# PCM2706_Bus_Powered_USB_DAC_3.net
KiCad netlist of a schematic drawn in Altium Designer
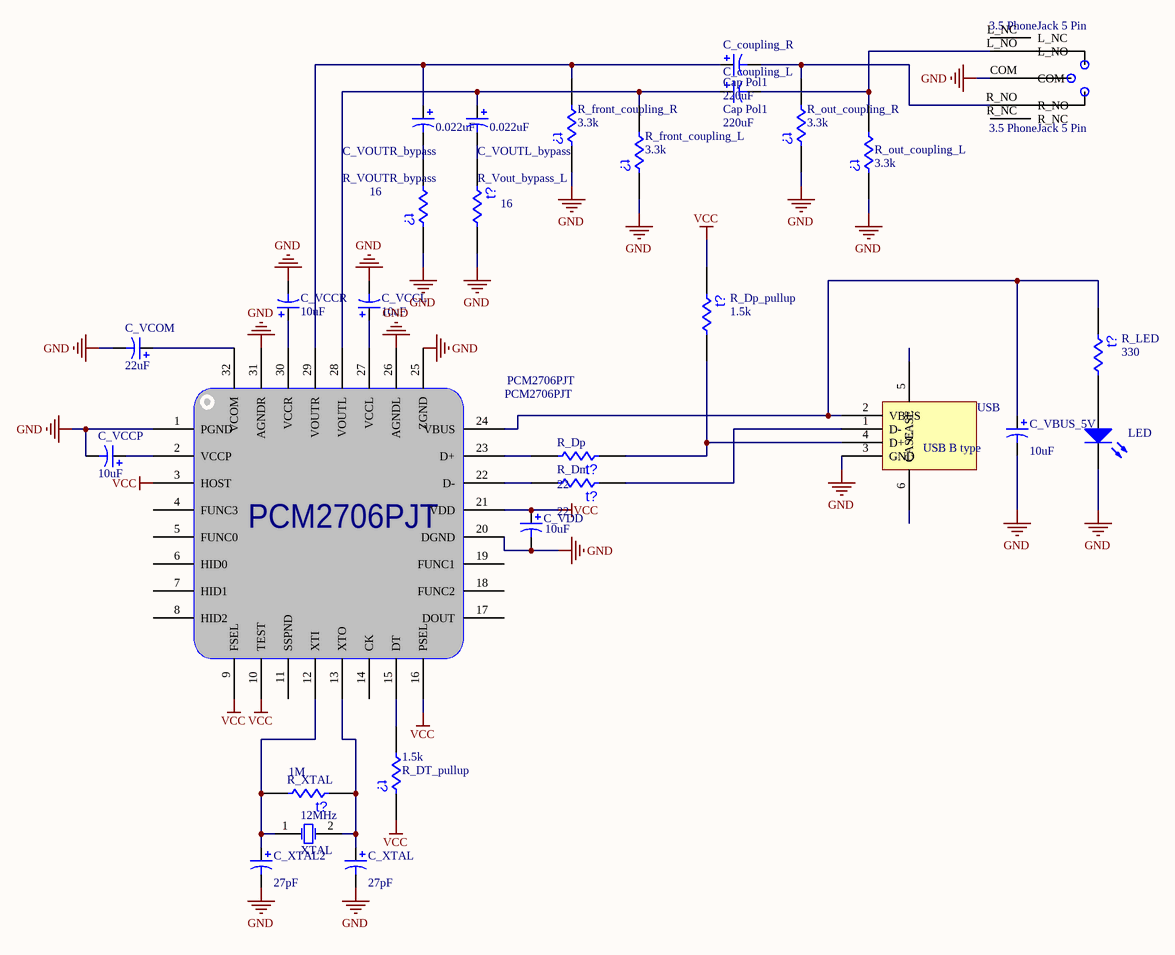
[diagram p0: PCM2706 Bus Powered USB DAC 3.SchDoc]

(export (version "E")
  (design (tool "Eeschema 10.0.6"))
  (components
    (comp (ref "1.5k")
      (value "R_DT_pullup")
      (footprint "6-0805_N")
      (description "Thermistor")
      (fields (field (name "PUBLISHER") "Altium Limited"))
      (libsource (lib "Miscellaneous Devices") (part "Res Thermal"))
    )
    (comp (ref "3.5 PhoneJack 5 Pin")
      (value "3.5 PhoneJack 5 Pin")
      (footprint "3.5 PhoneJack 5 Pin")
      (libsource (lib "misc") (part "3.5 PhoneJack 5 Pin"))
    )
    (comp (ref "12MHz")
      (value "XTAL")
      (footprint "12MHz Crystal OSC through hole")
      (description "Crystal Oscillator")
      (fields (field (name "PUBLISHER") "Altium Limited"))
      (libsource (lib "Miscellaneous Devices") (part "XTAL"))
    )
    (comp (ref "C_coupling_L")
      (value "Cap Pol1")
      (footprint "RB5-10.5_narrowed")
      (description "Polarized Capacitor (Radial)")
      (fields (field (name "ALTIUM_VALUE") "220uF") (field (name "PUBLISHER") "Altium Limited"))
      (libsource (lib "Miscellaneous Devices") (part "Cap Pol1"))
    )
    (comp (ref "C_coupling_R")
      (value "Cap Pol1")
      (footprint "RB5-10.5_narrowed")
      (description "Polarized Capacitor (Radial)")
      (fields (field (name "ALTIUM_VALUE") "220uF") (field (name "PUBLISHER") "Altium Limited"))
      (libsource (lib "Miscellaneous Devices") (part "Cap Pol1"))
    )
    (comp (ref "C_VBUS_5V")
      (value "10uF")
      (footprint "C0805")
      (description "Polarized Capacitor (Surface Mount)")
      (fields (field (name "PUBLISHER") "Altium Limited"))
      (libsource (lib "Miscellaneous Devices") (part "Cap Pol3"))
    )
    (comp (ref "C_VCCL")
      (value "10uF")
      (footprint "C0805")
      (description "Polarized Capacitor (Surface Mount)")
      (fields (field (name "PUBLISHER") "Altium Limited"))
      (libsource (lib "Miscellaneous Devices") (part "Cap Pol3"))
    )
    (comp (ref "C_VCCP")
      (value "10uF")
      (footprint "C0805")
      (description "Polarized Capacitor (Surface Mount)")
      (fields (field (name "PUBLISHER") "Altium Limited"))
      (libsource (lib "Miscellaneous Devices") (part "Cap Pol3"))
    )
    (comp (ref "C_VCCR")
      (value "10uF")
      (footprint "C0805")
      (description "Polarized Capacitor (Surface Mount)")
      (fields (field (name "PUBLISHER") "Altium Limited"))
      (libsource (lib "Miscellaneous Devices") (part "Cap Pol3"))
    )
    (comp (ref "C_VCOM")
      (value "22uF")
      (footprint "Tantalum 6032-28 case C kemet")
      (description "Polarized Capacitor (Surface Mount)")
      (fields (field (name "PUBLISHER") "Altium Limited"))
      (libsource (lib "Miscellaneous Devices") (part "Cap Pol3"))
    )
    (comp (ref "C_VDD")
      (value "10uF")
      (footprint "C0805")
      (description "Polarized Capacitor (Surface Mount)")
      (fields (field (name "PUBLISHER") "Altium Limited"))
      (libsource (lib "Miscellaneous Devices") (part "Cap Pol3"))
    )
    (comp (ref "C_VOUTL_bypass")
      (value "0.022uF")
      (footprint "C0805")
      (description "Polarized Capacitor (Surface Mount)")
      (fields (field (name "PUBLISHER") "Altium Limited"))
      (libsource (lib "Miscellaneous Devices") (part "Cap Pol3"))
    )
    (comp (ref "C_VOUTR_bypass")
      (value "0.022uF")
      (footprint "C0805")
      (description "Polarized Capacitor (Surface Mount)")
      (fields (field (name "PUBLISHER") "Altium Limited"))
      (libsource (lib "Miscellaneous Devices") (part "Cap Pol3"))
    )
    (comp (ref "C_XTAL")
      (value "27pF")
      (footprint "C0805")
      (description "Polarized Capacitor (Surface Mount)")
      (fields (field (name "PUBLISHER") "Altium Limited"))
      (libsource (lib "Miscellaneous Devices") (part "Cap Pol3"))
    )
    (comp (ref "C_XTAL2")
      (value "27pF")
      (footprint "C0805")
      (description "Polarized Capacitor (Surface Mount)")
      (fields (field (name "PUBLISHER") "Altium Limited"))
      (libsource (lib "Miscellaneous Devices") (part "Cap Pol3"))
    )
    (comp (ref "LED")
      (value "~")
      (footprint "6-0805_N_enlarge")
      (description "Typical RED, GREEN, YELLOW, AMBER GaAs LED")
      (fields (field (name "PUBLISHER") "Altium Limited"))
      (libsource (lib "Miscellaneous Devices") (part "LED2"))
    )
    (comp (ref "PCM2706PJT")
      (value "PCM2706PJT")
      (footprint "S-PQFP-N32-2mm-out")
      (libsource (lib "misc") (part "PCM2706PJT"))
    )
    (comp (ref "R_Dm")
      (value "22")
      (footprint "6-0805_N")
      (description "Thermistor")
      (fields (field (name "PUBLISHER") "Altium Limited"))
      (libsource (lib "Miscellaneous Devices") (part "Res Thermal"))
    )
    (comp (ref "R_Dp")
      (value "22")
      (footprint "6-0805_N")
      (description "Thermistor")
      (fields (field (name "PUBLISHER") "Altium Limited"))
      (libsource (lib "Miscellaneous Devices") (part "Res Thermal"))
    )
    (comp (ref "R_Dp_pullup")
      (value "1.5k")
      (footprint "6-0805_N")
      (description "Thermistor")
      (fields (field (name "PUBLISHER") "Altium Limited"))
      (libsource (lib "Miscellaneous Devices") (part "Res Thermal"))
    )
    (comp (ref "R_front_coupling_L")
      (value "3.3k")
      (footprint "6-0805_N")
      (description "Thermistor")
      (fields (field (name "PUBLISHER") "Altium Limited"))
      (libsource (lib "Miscellaneous Devices") (part "Res Thermal"))
    )
    (comp (ref "R_front_coupling_R")
      (value "3.3k")
      (footprint "6-0805_N")
      (description "Thermistor")
      (fields (field (name "PUBLISHER") "Altium Limited"))
      (libsource (lib "Miscellaneous Devices") (part "Res Thermal"))
    )
    (comp (ref "R_LED")
      (value "330")
      (footprint "6-0805_N")
      (description "Thermistor")
      (fields (field (name "PUBLISHER") "Altium Limited"))
      (libsource (lib "Miscellaneous Devices") (part "Res Thermal"))
    )
    (comp (ref "R_out_coupling_L")
      (value "3.3k")
      (footprint "6-0805_N")
      (description "Thermistor")
      (fields (field (name "PUBLISHER") "Altium Limited"))
      (libsource (lib "Miscellaneous Devices") (part "Res Thermal"))
    )
    (comp (ref "R_out_coupling_R")
      (value "3.3k")
      (footprint "6-0805_N")
      (description "Thermistor")
      (fields (field (name "PUBLISHER") "Altium Limited"))
      (libsource (lib "Miscellaneous Devices") (part "Res Thermal"))
    )
    (comp (ref "R_VOUTR_bypass")
      (value "16")
      (footprint "6-0805_N")
      (description "Thermistor")
      (fields (field (name "PUBLISHER") "Altium Limited"))
      (libsource (lib "Miscellaneous Devices") (part "Res Thermal"))
    )
    (comp (ref "R_Vout_bypass_L")
      (value "16")
      (footprint "6-0805_N")
      (description "Thermistor")
      (fields (field (name "PUBLISHER") "Altium Limited"))
      (libsource (lib "Miscellaneous Devices") (part "Res Thermal"))
    )
    (comp (ref "R_XTAL")
      (value "1M")
      (footprint "6-0805_N")
      (description "Thermistor")
      (fields (field (name "PUBLISHER") "Altium Limited"))
      (libsource (lib "Miscellaneous Devices") (part "Res Thermal"))
    )
    (comp (ref "USB")
      (value "USB B type")
      (footprint "USB2.5-2H4D")
      (libsource (lib "misc") (part "USB B type"))
    )
  )
  (nets
    (net (code "1") (name "GND") (class "Default")
      (node (ref "3.5 PhoneJack 5 Pin") (pin "COM") (pinfunction "COM_COM") (pintype "passive"))
      (node (ref "C_VBUS_5V") (pin "2") (pinfunction "2_2") (pintype "passive"))
      (node (ref "C_VCCL") (pin "2") (pinfunction "2_2") (pintype "passive"))
      (node (ref "C_VCCP") (pin "2") (pinfunction "2_2") (pintype "passive"))
      (node (ref "C_VCCR") (pin "2") (pinfunction "2_2") (pintype "passive"))
      (node (ref "C_VCOM") (pin "2") (pinfunction "2_2") (pintype "passive"))
      (node (ref "C_VDD") (pin "2") (pinfunction "2_2") (pintype "passive"))
      (node (ref "C_XTAL") (pin "2") (pinfunction "2_2") (pintype "passive"))
      (node (ref "C_XTAL2") (pin "2") (pinfunction "2_2") (pintype "passive"))
      (node (ref "LED") (pin "2") (pinfunction "K_2") (pintype "passive"))
      (node (ref "PCM2706PJT") (pin "1") (pinfunction "PGND_1") (pintype "passive"))
      (node (ref "PCM2706PJT") (pin "20") (pinfunction "DGND_20") (pintype "passive"))
      (node (ref "PCM2706PJT") (pin "25") (pinfunction "ZGND_25") (pintype "passive"))
      (node (ref "PCM2706PJT") (pin "26") (pinfunction "AGNDL_26") (pintype "passive"))
      (node (ref "PCM2706PJT") (pin "31") (pinfunction "AGNDR_31") (pintype "passive"))
      (node (ref "R_VOUTR_bypass") (pin "1") (pinfunction "1_1") (pintype "passive"))
      (node (ref "R_Vout_bypass_L") (pin "2") (pinfunction "2_2") (pintype "passive"))
      (node (ref "R_front_coupling_L") (pin "1") (pinfunction "1_1") (pintype "passive"))
      (node (ref "R_front_coupling_R") (pin "1") (pinfunction "1_1") (pintype "passive"))
      (node (ref "R_out_coupling_L") (pin "1") (pinfunction "1_1") (pintype "passive"))
      (node (ref "R_out_coupling_R") (pin "1") (pinfunction "1_1") (pintype "passive"))
      (node (ref "USB") (pin "3") (pinfunction "GND_3") (pintype "passive"))
    )
    (net (code "2") (name "Net-(3.5 PhoneJack 5 Pin-PadL_NO)") (class "Default")
      (node (ref "3.5 PhoneJack 5 Pin") (pin "L_NO") (pinfunction "L_NO_L_NO") (pintype "passive"))
      (node (ref "C_coupling_L") (pin "2") (pinfunction "2_2") (pintype "passive"))
      (node (ref "R_out_coupling_L") (pin "2") (pinfunction "2_2") (pintype "passive"))
    )
    (net (code "3") (name "Net-(3.5 PhoneJack 5 Pin-PadR_NO)") (class "Default")
      (node (ref "3.5 PhoneJack 5 Pin") (pin "R_NO") (pinfunction "R_NO_R_NO") (pintype "passive"))
      (node (ref "C_coupling_R") (pin "2") (pinfunction "2_2") (pintype "passive"))
      (node (ref "R_out_coupling_R") (pin "2") (pinfunction "2_2") (pintype "passive"))
    )
    (net (code "4") (name "Net-(12MHz-OSC1)") (class "Default")
      (node (ref "12MHz") (pin "1") (pinfunction "OSC1_1") (pintype "passive"))
      (node (ref "C_XTAL2") (pin "1") (pinfunction "1_1") (pintype "passive"))
      (node (ref "PCM2706PJT") (pin "12") (pinfunction "XTI_12") (pintype "passive"))
      (node (ref "R_XTAL") (pin "2") (pinfunction "2_2") (pintype "passive"))
    )
    (net (code "5") (name "Net-(12MHz-OSC2)") (class "Default")
      (node (ref "12MHz") (pin "2") (pinfunction "OSC2_2") (pintype "passive"))
      (node (ref "C_XTAL") (pin "1") (pinfunction "1_1") (pintype "passive"))
      (node (ref "PCM2706PJT") (pin "13") (pinfunction "XTO_13") (pintype "passive"))
      (node (ref "R_XTAL") (pin "1") (pinfunction "1_1") (pintype "passive"))
    )
    (net (code "6") (name "Net-(C_VOUTL_bypass-Pad2)") (class "Default")
      (node (ref "C_VOUTL_bypass") (pin "2") (pinfunction "2_2") (pintype "passive"))
      (node (ref "R_Vout_bypass_L") (pin "1") (pinfunction "1_1") (pintype "passive"))
    )
    (net (code "7") (name "Net-(C_VOUTR_bypass-Pad2)") (class "Default")
      (node (ref "C_VOUTR_bypass") (pin "2") (pinfunction "2_2") (pintype "passive"))
      (node (ref "R_VOUTR_bypass") (pin "2") (pinfunction "2_2") (pintype "passive"))
    )
    (net (code "8") (name "Net-(LED-A)") (class "Default")
      (node (ref "LED") (pin "1") (pinfunction "A_1") (pintype "passive"))
      (node (ref "R_LED") (pin "2") (pinfunction "2_2") (pintype "passive"))
    )
    (net (code "9") (name "Net-(PCM2706PJT-D+)") (class "Default")
      (node (ref "PCM2706PJT") (pin "23") (pinfunction "D+_23") (pintype "passive"))
      (node (ref "R_Dp") (pin "2") (pinfunction "2_2") (pintype "passive"))
    )
    (net (code "10") (name "Net-(PCM2706PJT-D-)") (class "Default")
      (node (ref "PCM2706PJT") (pin "22") (pinfunction "D-_22") (pintype "passive"))
      (node (ref "R_Dm") (pin "2") (pinfunction "2_2") (pintype "passive"))
    )
    (net (code "11") (name "Net-(PCM2706PJT-DT)") (class "Default")
      (node (ref "1.5k") (pin "2") (pinfunction "2_2") (pintype "passive"))
      (node (ref "PCM2706PJT") (pin "15") (pinfunction "DT_15") (pintype "passive"))
    )
    (net (code "12") (name "Net-(PCM2706PJT-VBUS)") (class "Default")
      (node (ref "C_VBUS_5V") (pin "1") (pinfunction "1_1") (pintype "passive"))
      (node (ref "PCM2706PJT") (pin "24") (pinfunction "VBUS_24") (pintype "passive"))
      (node (ref "R_LED") (pin "1") (pinfunction "1_1") (pintype "passive"))
      (node (ref "USB") (pin "2") (pinfunction "VBUS_2") (pintype "passive"))
    )
    (net (code "13") (name "Net-(PCM2706PJT-VCCL)") (class "Default")
      (node (ref "C_VCCL") (pin "1") (pinfunction "1_1") (pintype "passive"))
      (node (ref "PCM2706PJT") (pin "27") (pinfunction "VCCL_27") (pintype "passive"))
    )
    (net (code "14") (name "Net-(PCM2706PJT-VCCP)") (class "Default")
      (node (ref "C_VCCP") (pin "1") (pinfunction "1_1") (pintype "passive"))
      (node (ref "PCM2706PJT") (pin "2") (pinfunction "VCCP_2") (pintype "passive"))
    )
    (net (code "15") (name "Net-(PCM2706PJT-VCCR)") (class "Default")
      (node (ref "C_VCCR") (pin "1") (pinfunction "1_1") (pintype "passive"))
      (node (ref "PCM2706PJT") (pin "30") (pinfunction "VCCR_30") (pintype "passive"))
    )
    (net (code "16") (name "Net-(PCM2706PJT-VCOM)") (class "Default")
      (node (ref "C_VCOM") (pin "1") (pinfunction "1_1") (pintype "passive"))
      (node (ref "PCM2706PJT") (pin "32") (pinfunction "VCOM_32") (pintype "passive"))
    )
    (net (code "17") (name "Net-(PCM2706PJT-VOUTL)") (class "Default")
      (node (ref "C_VOUTL_bypass") (pin "1") (pinfunction "1_1") (pintype "passive"))
      (node (ref "C_coupling_L") (pin "1") (pinfunction "1_1") (pintype "passive"))
      (node (ref "PCM2706PJT") (pin "28") (pinfunction "VOUTL_28") (pintype "passive"))
      (node (ref "R_front_coupling_L") (pin "2") (pinfunction "2_2") (pintype "passive"))
    )
    (net (code "18") (name "Net-(PCM2706PJT-VOUTR)") (class "Default")
      (node (ref "C_VOUTR_bypass") (pin "1") (pinfunction "1_1") (pintype "passive"))
      (node (ref "C_coupling_R") (pin "1") (pinfunction "1_1") (pintype "passive"))
      (node (ref "PCM2706PJT") (pin "29") (pinfunction "VOUTR_29") (pintype "passive"))
      (node (ref "R_front_coupling_R") (pin "2") (pinfunction "2_2") (pintype "passive"))
    )
    (net (code "19") (name "Net-(USB-D+)") (class "Default")
      (node (ref "R_Dp") (pin "1") (pinfunction "1_1") (pintype "passive"))
      (node (ref "R_Dp_pullup") (pin "2") (pinfunction "2_2") (pintype "passive"))
      (node (ref "USB") (pin "4") (pinfunction "D+_4") (pintype "passive"))
    )
    (net (code "20") (name "Net-(USB-D-)") (class "Default")
      (node (ref "R_Dm") (pin "1") (pinfunction "1_1") (pintype "passive"))
      (node (ref "USB") (pin "1") (pinfunction "D-_1") (pintype "passive"))
    )
    (net (code "21") (name "VCC") (class "Default")
      (node (ref "1.5k") (pin "1") (pinfunction "1_1") (pintype "passive"))
      (node (ref "C_VDD") (pin "1") (pinfunction "1_1") (pintype "passive"))
      (node (ref "PCM2706PJT") (pin "10") (pinfunction "TEST_10") (pintype "passive"))
      (node (ref "PCM2706PJT") (pin "16") (pinfunction "PSEL_16") (pintype "passive"))
      (node (ref "PCM2706PJT") (pin "21") (pinfunction "VDD_21") (pintype "passive"))
      (node (ref "PCM2706PJT") (pin "3") (pinfunction "HOST_3") (pintype "passive"))
      (node (ref "PCM2706PJT") (pin "9") (pinfunction "FSEL_9") (pintype "passive"))
      (node (ref "R_Dp_pullup") (pin "1") (pinfunction "1_1") (pintype "passive"))
    )
    (net (code "22") (name "unconnected-(3.5 PhoneJack 5 Pin-PadL_NC)") (class "Default")
      (node (ref "3.5 PhoneJack 5 Pin") (pin "L_NC") (pinfunction "L_NC_L_NC") (pintype "passive"))
    )
    (net (code "23") (name "unconnected-(3.5 PhoneJack 5 Pin-PadR_NC)") (class "Default")
      (node (ref "3.5 PhoneJack 5 Pin") (pin "R_NC") (pinfunction "R_NC_R_NC") (pintype "passive"))
    )
    (net (code "24") (name "unconnected-(PCM2706PJT-CK-Pad14)") (class "Default")
      (node (ref "PCM2706PJT") (pin "14") (pinfunction "CK_14") (pintype "passive"))
    )
    (net (code "25") (name "unconnected-(PCM2706PJT-DOUT-Pad17)") (class "Default")
      (node (ref "PCM2706PJT") (pin "17") (pinfunction "DOUT_17") (pintype "passive"))
    )
    (net (code "26") (name "unconnected-(PCM2706PJT-FUNC0-Pad5)") (class "Default")
      (node (ref "PCM2706PJT") (pin "5") (pinfunction "FUNC0_5") (pintype "passive"))
    )
    (net (code "27") (name "unconnected-(PCM2706PJT-FUNC1-Pad19)") (class "Default")
      (node (ref "PCM2706PJT") (pin "19") (pinfunction "FUNC1_19") (pintype "passive"))
    )
    (net (code "28") (name "unconnected-(PCM2706PJT-FUNC2-Pad18)") (class "Default")
      (node (ref "PCM2706PJT") (pin "18") (pinfunction "FUNC2_18") (pintype "passive"))
    )
    (net (code "29") (name "unconnected-(PCM2706PJT-FUNC3-Pad4)") (class "Default")
      (node (ref "PCM2706PJT") (pin "4") (pinfunction "FUNC3_4") (pintype "passive"))
    )
    (net (code "30") (name "unconnected-(PCM2706PJT-HID0-Pad6)") (class "Default")
      (node (ref "PCM2706PJT") (pin "6") (pinfunction "HID0_6") (pintype "passive"))
    )
    (net (code "31") (name "unconnected-(PCM2706PJT-HID1-Pad7)") (class "Default")
      (node (ref "PCM2706PJT") (pin "7") (pinfunction "HID1_7") (pintype "passive"))
    )
    (net (code "32") (name "unconnected-(PCM2706PJT-HID2-Pad8)") (class "Default")
      (node (ref "PCM2706PJT") (pin "8") (pinfunction "HID2_8") (pintype "passive"))
    )
    (net (code "33") (name "unconnected-(PCM2706PJT-SSPND-Pad11)") (class "Default")
      (node (ref "PCM2706PJT") (pin "11") (pinfunction "SSPND_11") (pintype "passive"))
    )
    (net (code "34") (name "unconnected-(USB-CASE-Pad5)") (class "Default")
      (node (ref "USB") (pin "5") (pinfunction "CASE_5") (pintype "passive"))
    )
    (net (code "35") (name "unconnected-(USB-CASE-Pad6)") (class "Default")
      (node (ref "USB") (pin "6") (pinfunction "CASE_6") (pintype "passive"))
    )
  )
)
